# zdrive.net
KiCad netlist of a schematic drawn in EAGLE
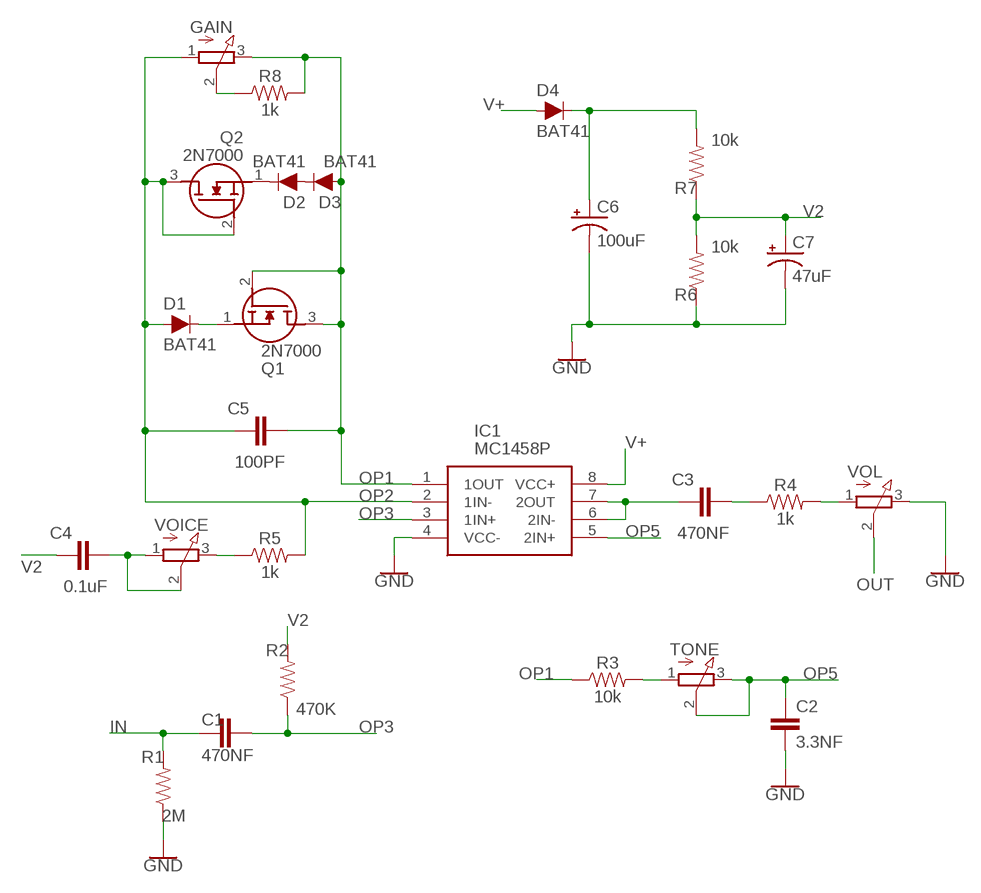
[diagram p0: schematic, sheet 1]

(export (version "E")
  (design (tool "Eeschema 10.0.6"))
  (components
    (comp (ref "C1")
      (value "470NF")
      (footprint "eagle-import:CAP-PTH-SMALL-KIT")
      (libsource (lib "eagle-import") (part "470NF"))
    )
    (comp (ref "C2")
      (value "3.3NF")
      (footprint "eagle-import:CAP-PTH-SMALL-KIT")
      (libsource (lib "eagle-import") (part "3.3NF"))
    )
    (comp (ref "C3")
      (value "470NF")
      (footprint "eagle-import:CAP-PTH-SMALL-KIT")
      (libsource (lib "eagle-import") (part "470NF"))
    )
    (comp (ref "C4")
      (value "0.1uF")
      (footprint "eagle-import:CAP-PTH-SMALL-KIT")
      (libsource (lib "eagle-import") (part "0.1UF-KIT-EZ-50V-20%"))
    )
    (comp (ref "C5")
      (value "100PF")
      (footprint "eagle-import:CAP-PTH-SMALL-KIT")
      (libsource (lib "eagle-import") (part "100PF"))
    )
    (comp (ref "C6")
      (value "100uF")
      (footprint "eagle-import:CPOL-RADIAL-2.5MM-6.5MM")
      (libsource (lib "eagle-import") (part "100UF-POLAR-RADIAL-2.5MM-25V-20%"))
    )
    (comp (ref "C7")
      (value "47uF")
      (footprint "eagle-import:CPOL-RADIAL-2.5MM-6.5MM")
      (libsource (lib "eagle-import") (part "47UF-POLAR-RADIAL-2.5MM-25V-20%"))
    )
    (comp (ref "D1")
      (value "BAT41")
      (footprint "eagle-import:DIODE-1N4001-KIT")
      (libsource (lib "eagle-import") (part "DIODE-KIT2"))
    )
    (comp (ref "D2")
      (value "BAT41")
      (footprint "eagle-import:DIODE-1N4001-KIT")
      (libsource (lib "eagle-import") (part "DIODE-KIT2"))
    )
    (comp (ref "D3")
      (value "BAT41")
      (footprint "eagle-import:DIODE-1N4001-KIT")
      (libsource (lib "eagle-import") (part "DIODE-KIT2"))
    )
    (comp (ref "D4")
      (value "BAT41")
      (footprint "eagle-import:DIODE-1N4001-KIT")
      (libsource (lib "eagle-import") (part "DIODE-KIT2"))
    )
    (comp (ref "GAIN")
      (value "3RP/1610N")
      (footprint "eagle-import:3RP_1610N")
      (libsource (lib "eagle-import") (part "3RP/1610N"))
    )
    (comp (ref "IC1")
      (value "MC1458P")
      (footprint "eagle-import:DIP794W53P254L959H508Q8N")
      (fields (field (name "MOUSER_PART_NUMBER") "595-MC1458P"))
      (libsource (lib "eagle-import") (part "MC1458P"))
    )
    (comp (ref "Q1")
      (value "2N7000")
      (footprint "eagle-import:TO-92_(TO-226)")
      (fields (field (name "MOUSER_PART_NUMBER") "512-2N7000"))
      (libsource (lib "eagle-import") (part "2N7000"))
    )
    (comp (ref "Q2")
      (value "2N7000")
      (footprint "eagle-import:TO-92_(TO-226)")
      (fields (field (name "MOUSER_PART_NUMBER") "512-2N7000"))
      (libsource (lib "eagle-import") (part "2N7000"))
    )
    (comp (ref "R1")
      (value "2M")
      (footprint "eagle-import:AXIAL-0.3")
      (libsource (lib "eagle-import") (part "2MOHM-HORIZ-1/4W-5%"))
    )
    (comp (ref "R2")
      (value "470K")
      (footprint "eagle-import:AXIAL-0.3")
      (libsource (lib "eagle-import") (part "470K-HORIZ-1/4W-5%"))
    )
    (comp (ref "R3")
      (value "10k")
      (footprint "eagle-import:AXIAL-0.3")
      (libsource (lib "eagle-import") (part "10KOHM-HORIZ-1/4W-5%"))
    )
    (comp (ref "R4")
      (value "1k")
      (footprint "eagle-import:AXIAL-0.3")
      (libsource (lib "eagle-import") (part "1KOHM-HORIZ-1/4W-5%"))
    )
    (comp (ref "R5")
      (value "1k")
      (footprint "eagle-import:AXIAL-0.3")
      (libsource (lib "eagle-import") (part "1KOHM-HORIZ-1/4W-5%"))
    )
    (comp (ref "R6")
      (value "10k")
      (footprint "eagle-import:AXIAL-0.3")
      (libsource (lib "eagle-import") (part "10KOHM-HORIZ-1/4W-5%"))
    )
    (comp (ref "R7")
      (value "10k")
      (footprint "eagle-import:AXIAL-0.3")
      (libsource (lib "eagle-import") (part "10KOHM-HORIZ-1/4W-5%"))
    )
    (comp (ref "R8")
      (value "1k")
      (footprint "eagle-import:AXIAL-0.3")
      (libsource (lib "eagle-import") (part "1KOHM-HORIZ-1/4W-5%"))
    )
    (comp (ref "TONE")
      (value "3RP/1610N")
      (footprint "eagle-import:3RP_1610N")
      (libsource (lib "eagle-import") (part "3RP/1610N"))
    )
    (comp (ref "VOICE")
      (value "3RP/1610N")
      (footprint "eagle-import:3RP_1610N")
      (libsource (lib "eagle-import") (part "3RP/1610N"))
    )
    (comp (ref "VOL")
      (value "3RP/1610N")
      (footprint "eagle-import:3RP_1610N")
      (libsource (lib "eagle-import") (part "3RP/1610N"))
    )
  )
  (nets
    (net (code "1") (name "/IN") (class "Default")
      (node (ref "C1") (pin "2") (pinfunction "2_2") (pintype "passive"))
      (node (ref "R1") (pin "P$2") (pinfunction "2_P$2") (pintype "passive"))
    )
    (net (code "2") (name "/OP1") (class "Default")
      (node (ref "C5") (pin "2") (pinfunction "2_2") (pintype "passive"))
      (node (ref "D3") (pin "A") (pinfunction "A_A") (pintype "passive"))
      (node (ref "GAIN") (pin "3") (pinfunction "E_3") (pintype "passive"))
      (node (ref "IC1") (pin "1") (pinfunction "1OUT_1") (pintype "output"))
      (node (ref "Q1") (pin "2") (pinfunction "G_2") (pintype "bidirectional"))
      (node (ref "Q1") (pin "3") (pinfunction "D_3") (pintype "bidirectional"))
      (node (ref "R3") (pin "P$1") (pinfunction "1_P$1") (pintype "passive"))
      (node (ref "R8") (pin "P$2") (pinfunction "2_P$2") (pintype "passive"))
    )
    (net (code "3") (name "/OP2") (class "Default")
      (node (ref "C5") (pin "1") (pinfunction "1_1") (pintype "passive"))
      (node (ref "D1") (pin "A") (pinfunction "A_A") (pintype "passive"))
      (node (ref "GAIN") (pin "1") (pinfunction "A_1") (pintype "passive"))
      (node (ref "IC1") (pin "2") (pinfunction "1IN-_2") (pintype "input"))
      (node (ref "Q2") (pin "2") (pinfunction "G_2") (pintype "bidirectional"))
      (node (ref "Q2") (pin "3") (pinfunction "D_3") (pintype "bidirectional"))
      (node (ref "R5") (pin "P$2") (pinfunction "2_P$2") (pintype "passive"))
    )
    (net (code "4") (name "/OP3") (class "Default")
      (node (ref "C1") (pin "1") (pinfunction "1_1") (pintype "passive"))
      (node (ref "IC1") (pin "3") (pinfunction "1IN+_3") (pintype "input"))
      (node (ref "R2") (pin "P$1") (pinfunction "1_P$1") (pintype "passive"))
    )
    (net (code "5") (name "/OP5") (class "Default")
      (node (ref "C2") (pin "1") (pinfunction "1_1") (pintype "passive"))
      (node (ref "IC1") (pin "5") (pinfunction "2IN+_5") (pintype "input"))
      (node (ref "TONE") (pin "2") (pinfunction "S_2") (pintype "passive"))
      (node (ref "TONE") (pin "3") (pinfunction "E_3") (pintype "passive"))
    )
    (net (code "6") (name "/OUT") (class "Default")
      (node (ref "VOL") (pin "2") (pinfunction "S_2") (pintype "passive"))
    )
    (net (code "7") (name "/V+") (class "Default")
      (node (ref "C6") (pin "1") (pinfunction "+_1") (pintype "passive"))
      (node (ref "D4") (pin "A") (pinfunction "A_A") (pintype "passive"))
      (node (ref "D4") (pin "C") (pinfunction "C_C") (pintype "passive"))
      (node (ref "IC1") (pin "8") (pinfunction "VCC+_8") (pintype "power_in"))
      (node (ref "R7") (pin "P$2") (pinfunction "2_P$2") (pintype "passive"))
    )
    (net (code "8") (name "/V2") (class "Default")
      (node (ref "C4") (pin "1") (pinfunction "1_1") (pintype "passive"))
      (node (ref "C7") (pin "1") (pinfunction "+_1") (pintype "passive"))
      (node (ref "R2") (pin "P$2") (pinfunction "2_P$2") (pintype "passive"))
      (node (ref "R6") (pin "P$2") (pinfunction "2_P$2") (pintype "passive"))
      (node (ref "R7") (pin "P$1") (pinfunction "1_P$1") (pintype "passive"))
    )
    (net (code "9") (name "GND") (class "Default")
      (node (ref "C2") (pin "2") (pinfunction "2_2") (pintype "passive"))
      (node (ref "C6") (pin "2") (pinfunction "-_2") (pintype "passive"))
      (node (ref "C7") (pin "2") (pinfunction "-_2") (pintype "passive"))
      (node (ref "IC1") (pin "4") (pinfunction "VCC-_4") (pintype "power_in"))
      (node (ref "R1") (pin "P$1") (pinfunction "1_P$1") (pintype "passive"))
      (node (ref "R6") (pin "P$1") (pinfunction "1_P$1") (pintype "passive"))
      (node (ref "VOL") (pin "3") (pinfunction "E_3") (pintype "passive"))
    )
    (net (code "10") (name "Net-(D2-PadA)") (class "Default")
      (node (ref "D2") (pin "A") (pinfunction "A_A") (pintype "passive"))
      (node (ref "D3") (pin "C") (pinfunction "C_C") (pintype "passive"))
    )
    (net (code "11") (name "Net-(GAIN-S)") (class "Default")
      (node (ref "GAIN") (pin "2") (pinfunction "S_2") (pintype "passive"))
      (node (ref "R8") (pin "P$1") (pinfunction "1_P$1") (pintype "passive"))
    )
    (net (code "12") (name "Net-(IC1-2IN-)") (class "Default")
      (node (ref "C3") (pin "1") (pinfunction "1_1") (pintype "passive"))
      (node (ref "IC1") (pin "6") (pinfunction "2IN-_6") (pintype "input"))
      (node (ref "IC1") (pin "7") (pinfunction "2OUT_7") (pintype "output"))
    )
    (net (code "13") (name "Net-(Q1-S)") (class "Default")
      (node (ref "D1") (pin "C") (pinfunction "C_C") (pintype "passive"))
      (node (ref "Q1") (pin "1") (pinfunction "S_1") (pintype "bidirectional"))
    )
    (net (code "14") (name "Net-(Q2-S)") (class "Default")
      (node (ref "D2") (pin "C") (pinfunction "C_C") (pintype "passive"))
      (node (ref "Q2") (pin "1") (pinfunction "S_1") (pintype "bidirectional"))
    )
    (net (code "15") (name "Net-(R3-2)") (class "Default")
      (node (ref "R3") (pin "P$2") (pinfunction "2_P$2") (pintype "passive"))
      (node (ref "TONE") (pin "1") (pinfunction "A_1") (pintype "passive"))
    )
    (net (code "16") (name "Net-(R4-1)") (class "Default")
      (node (ref "C3") (pin "2") (pinfunction "2_2") (pintype "passive"))
      (node (ref "R4") (pin "P$1") (pinfunction "1_P$1") (pintype "passive"))
    )
    (net (code "17") (name "Net-(R4-2)") (class "Default")
      (node (ref "R4") (pin "P$2") (pinfunction "2_P$2") (pintype "passive"))
      (node (ref "VOL") (pin "1") (pinfunction "A_1") (pintype "passive"))
    )
    (net (code "18") (name "Net-(R5-1)") (class "Default")
      (node (ref "R5") (pin "P$1") (pinfunction "1_P$1") (pintype "passive"))
      (node (ref "VOICE") (pin "3") (pinfunction "E_3") (pintype "passive"))
    )
    (net (code "19") (name "Net-(VOICE-A)") (class "Default")
      (node (ref "C4") (pin "2") (pinfunction "2_2") (pintype "passive"))
      (node (ref "VOICE") (pin "1") (pinfunction "A_1") (pintype "passive"))
      (node (ref "VOICE") (pin "2") (pinfunction "S_2") (pintype "passive"))
    )
  )
)
